# Relay_channel.net
KiCad netlist of a schematic drawn in Altium Designer
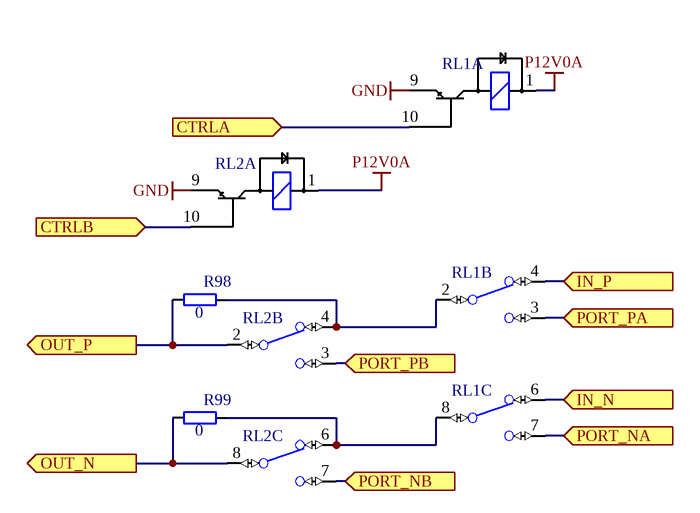
[diagram p0: Relay_channel.SchDoc]

(export (version "E")
  (design (tool "Eeschema 10.0.6"))
  (components
    (comp (ref "R98")
      (value "0")
      (footprint "RESC1608X55N")
      (description "Resistor")
      (fields
        (field (name "PART NUMBER") "R0603_0R_JUMPER")
        (field (name "MANUFACTURER") "GENERIC")
        (field (name "AUTHOR") "CERN DEM JLC")
      )
      (libsource (lib "Resistors") (part "Resistor"))
    )
    (comp (ref "R99")
      (value "0")
      (footprint "RESC1608X55N")
      (description "Resistor")
      (fields
        (field (name "PART NUMBER") "R0603_0R_JUMPER")
        (field (name "MANUFACTURER") "GENERIC")
        (field (name "AUTHOR") "CERN DEM JLC")
      )
      (libsource (lib "Resistors") (part "Resistor"))
    )
    (comp (ref "RL1")
      (value "TELEDYNE_712TN")
      (footprint "REL_TELEDYNE_712TN")
      (description "DPDT Non-latching Commercial Sensitive Basic Relay")
      (fields
        (field (name "PART NUMBER") "REL_TELEDYNE__712TN-12")
        (field (name "MANUFACTURER") "TELEDYNE")
        (field (name "AUTHOR") "GK")
      )
      (libsource (lib "Switches_Relays") (part "REL_TELEDYNE_712TN-12"))
    )
    (comp (ref "RL2")
      (value "TELEDYNE_712TN")
      (footprint "REL_TELEDYNE_712TN")
      (description "DPDT Non-latching Commercial Sensitive Basic Relay")
      (fields
        (field (name "PART NUMBER") "REL_TELEDYNE__712TN-12")
        (field (name "MANUFACTURER") "TELEDYNE")
        (field (name "AUTHOR") "GK")
      )
      (libsource (lib "Switches_Relays") (part "REL_TELEDYNE_712TN-12"))
    )
  )
  (nets
    (net (code "1") (name "/CTRLA") (class "Default")
      (node (ref "RL1") (pin "10") (pinfunction "10_10") (pintype "passive"))
    )
    (net (code "2") (name "/CTRLB") (class "Default")
      (node (ref "RL2") (pin "10") (pinfunction "10_10") (pintype "passive"))
    )
    (net (code "3") (name "/IN_N") (class "Default")
      (node (ref "RL1") (pin "6") (pinfunction "NC_6") (pintype "bidirectional"))
    )
    (net (code "4") (name "/IN_P") (class "Default")
      (node (ref "RL1") (pin "4") (pinfunction "NC_4") (pintype "bidirectional"))
    )
    (net (code "5") (name "/OUT_N") (class "Default")
      (node (ref "R99") (pin "1") (pinfunction "1_1") (pintype "passive"))
      (node (ref "RL2") (pin "8") (pinfunction "C_8") (pintype "bidirectional"))
    )
    (net (code "6") (name "/OUT_P") (class "Default")
      (node (ref "R98") (pin "1") (pinfunction "1_1") (pintype "passive"))
      (node (ref "RL2") (pin "2") (pinfunction "C_2") (pintype "bidirectional"))
    )
    (net (code "7") (name "/PORT_NA") (class "Default")
      (node (ref "RL1") (pin "7") (pinfunction "NO_7") (pintype "bidirectional"))
    )
    (net (code "8") (name "/PORT_NB") (class "Default")
      (node (ref "RL2") (pin "7") (pinfunction "NO_7") (pintype "bidirectional"))
    )
    (net (code "9") (name "/PORT_PA") (class "Default")
      (node (ref "RL1") (pin "3") (pinfunction "NO_3") (pintype "bidirectional"))
    )
    (net (code "10") (name "/PORT_PB") (class "Default")
      (node (ref "RL2") (pin "3") (pinfunction "NO_3") (pintype "bidirectional"))
    )
    (net (code "11") (name "GND") (class "Default")
      (node (ref "RL1") (pin "9") (pinfunction "9_9") (pintype "passive"))
      (node (ref "RL2") (pin "9") (pinfunction "9_9") (pintype "passive"))
    )
    (net (code "12") (name "Net-(RL1B-C)") (class "Default")
      (node (ref "R98") (pin "2") (pinfunction "2_2") (pintype "passive"))
      (node (ref "RL1") (pin "2") (pinfunction "C_2") (pintype "bidirectional"))
      (node (ref "RL2") (pin "4") (pinfunction "NC_4") (pintype "bidirectional"))
    )
    (net (code "13") (name "Net-(RL1C-C)") (class "Default")
      (node (ref "R99") (pin "2") (pinfunction "2_2") (pintype "passive"))
      (node (ref "RL1") (pin "8") (pinfunction "C_8") (pintype "bidirectional"))
      (node (ref "RL2") (pin "6") (pinfunction "NC_6") (pintype "bidirectional"))
    )
    (net (code "14") (name "P12V0A") (class "Default")
      (node (ref "RL1") (pin "1") (pinfunction "1_1") (pintype "passive"))
      (node (ref "RL2") (pin "1") (pinfunction "1_1") (pintype "passive"))
    )
  )
)
